# Connector_A.net
KiCad netlist of a schematic drawn in Altium Designer
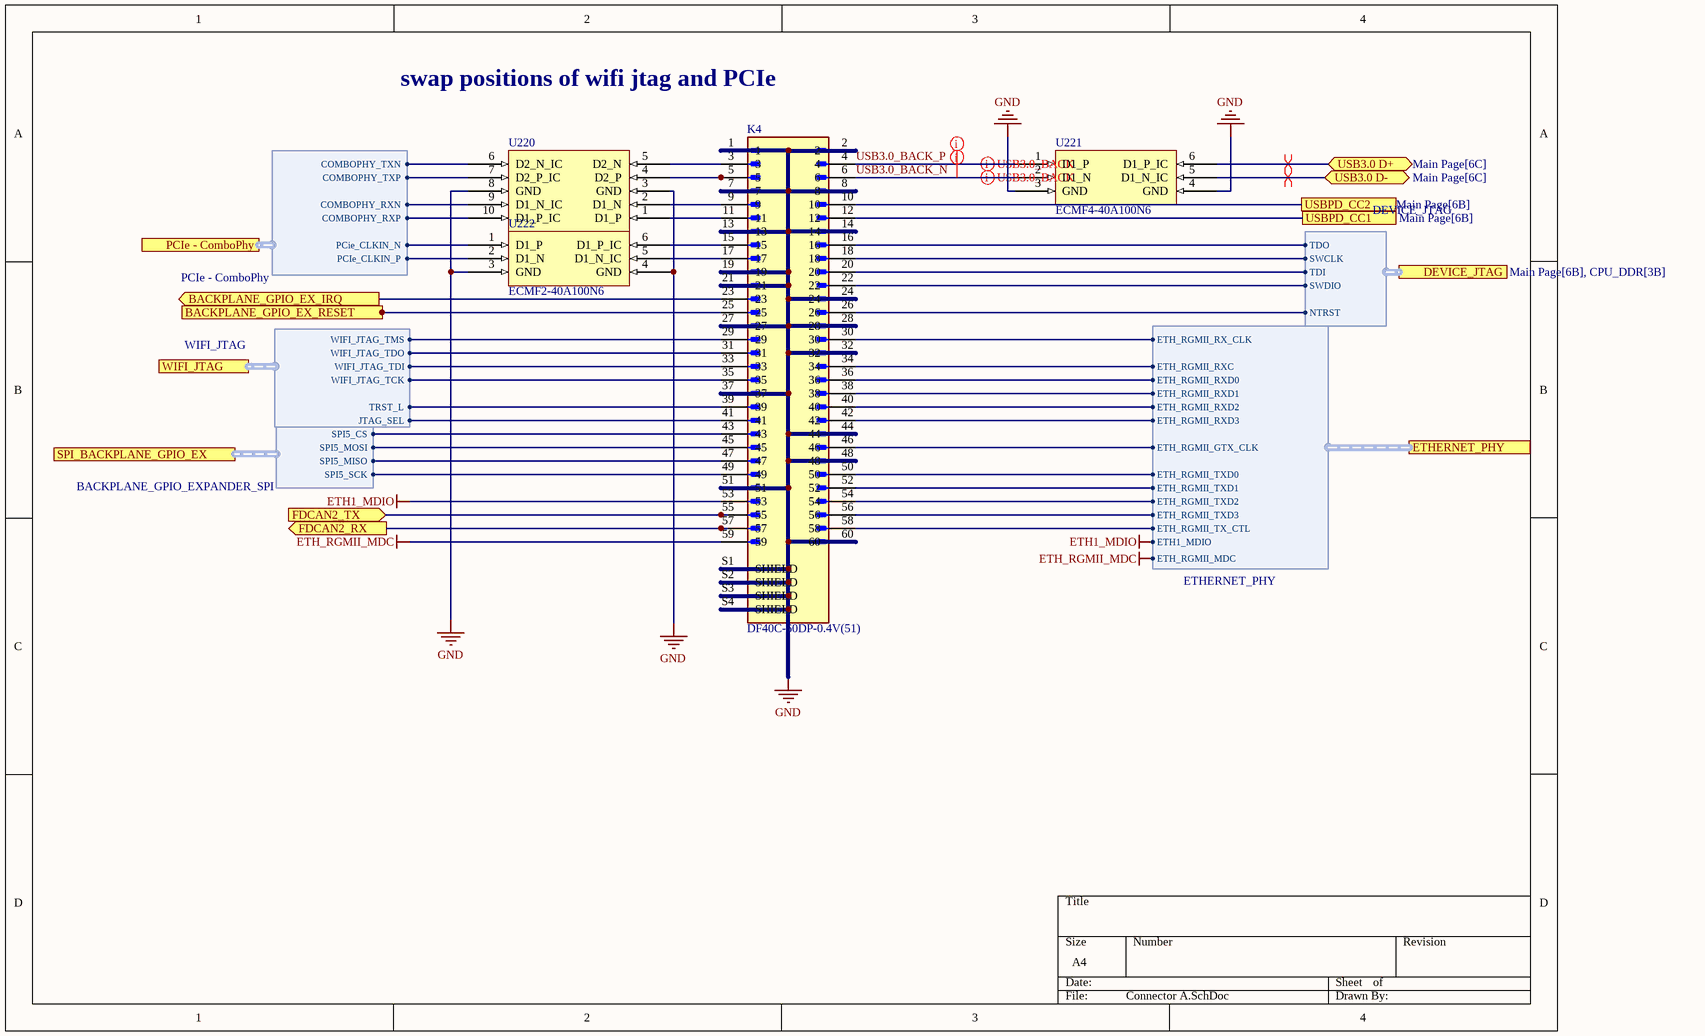
[diagram p0: Connector A.SchDoc]

(export (version "E")
  (design (tool "Eeschema 10.0.6"))
  (components
    (comp (ref "K4")
      (value "DF40C-60DP-0.4V(51)")
      (footprint "HIROSE_DF40C-60DP-0.4V(51)")
      (description "60 Position Connector Plug, Outer Shroud Contacts Surface Mount Gold")
      (fields (field (name "MF") "Hirose Electric"))
      (libsource (lib "Gesturelink Schematic Library") (part "DF40C-60DP-0.4V(51)"))
    )
    (comp (ref "U220")
      (value "ECMF4-40A100N10")
      (footprint "ECMF4-40A100N10")
      (description "4 Line Common Mode Choke Surface Mount 100mA DCR 3Ohm (Typ)")
      (libsource (lib "Gesturelink Schematic Library") (part "ECMF4-40A100N10"))
    )
    (comp (ref "U221")
      (value "ECMF4-40A100N6")
      (footprint "ECMF2-40A100N6")
      (description "2 Line Common Mode Choke Surface Mount 100mA DCR 3Ohm (Typ)")
      (libsource (lib "Gesturelink Schematic Library") (part "ECMF4-40A100N6"))
    )
    (comp (ref "U222")
      (value "ECMF2-40A100N6")
      (footprint "ECMF2-40A100N6")
      (description "2 Line Common Mode Choke Surface Mount 100mA DCR 3Ohm (Typ)")
      (libsource (lib "Gesturelink Schematic Library") (part "ECMF2-40A100N6"))
    )
  )
  (nets
    (net (code "8") (name "/BACKPLANE_GPIO_EX_IRQ") (class "Default")
      (node (ref "K4") (pin "23") (pinfunction "23_23") (pintype "passive"))
    )
    (net (code "9") (name "/BACKPLANE_GPIO_EX_RESET") (class "Default")
      (node (ref "K4") (pin "25") (pinfunction "25_25") (pintype "passive"))
    )
    (net (code "10") (name "/COMBOPHY_RXN") (class "Default")
      (node (ref "U220") (pin "9") (pinfunction "D1_N_IC_9") (pintype "input"))
    )
    (net (code "11") (name "/COMBOPHY_RXP") (class "Default")
      (node (ref "U220") (pin "10") (pinfunction "D1_P_IC_10") (pintype "input"))
    )
    (net (code "12") (name "/COMBOPHY_TXN") (class "Default")
      (node (ref "U220") (pin "6") (pinfunction "D2_N_IC_6") (pintype "input"))
    )
    (net (code "13") (name "/COMBOPHY_TXP") (class "Default")
      (node (ref "U220") (pin "7") (pinfunction "D2_P_IC_7") (pintype "input"))
    )
    (net (code "14") (name "/ETH_RGMII_GTX_CLK") (class "Default")
      (node (ref "K4") (pin "46") (pinfunction "46_46") (pintype "passive"))
    )
    (net (code "15") (name "/ETH_RGMII_RXC") (class "Default")
      (node (ref "K4") (pin "34") (pinfunction "34_34") (pintype "passive"))
    )
    (net (code "16") (name "/ETH_RGMII_RXD0") (class "Default")
      (node (ref "K4") (pin "36") (pinfunction "36_36") (pintype "passive"))
    )
    (net (code "17") (name "/ETH_RGMII_RXD1") (class "Default")
      (node (ref "K4") (pin "38") (pinfunction "38_38") (pintype "passive"))
    )
    (net (code "18") (name "/ETH_RGMII_RXD2") (class "Default")
      (node (ref "K4") (pin "40") (pinfunction "40_40") (pintype "passive"))
    )
    (net (code "19") (name "/ETH_RGMII_RXD3") (class "Default")
      (node (ref "K4") (pin "42") (pinfunction "42_42") (pintype "passive"))
    )
    (net (code "20") (name "/ETH_RGMII_RX_CLK") (class "Default")
      (node (ref "K4") (pin "30") (pinfunction "30_30") (pintype "passive"))
    )
    (net (code "21") (name "/ETH_RGMII_TXD0") (class "Default")
      (node (ref "K4") (pin "50") (pinfunction "50_50") (pintype "passive"))
    )
    (net (code "22") (name "/ETH_RGMII_TXD1") (class "Default")
      (node (ref "K4") (pin "52") (pinfunction "52_52") (pintype "passive"))
    )
    (net (code "23") (name "/ETH_RGMII_TXD2") (class "Default")
      (node (ref "K4") (pin "54") (pinfunction "54_54") (pintype "passive"))
    )
    (net (code "24") (name "/ETH_RGMII_TXD3") (class "Default")
      (node (ref "K4") (pin "56") (pinfunction "56_56") (pintype "passive"))
    )
    (net (code "25") (name "/ETH_RGMII_TX_CTL") (class "Default")
      (node (ref "K4") (pin "58") (pinfunction "58_58") (pintype "passive"))
    )
    (net (code "26") (name "/FDCAN2_RX") (class "Default")
      (node (ref "K4") (pin "57") (pinfunction "57_57") (pintype "passive"))
    )
    (net (code "27") (name "/FDCAN2_TX") (class "Default")
      (node (ref "K4") (pin "55") (pinfunction "55_55") (pintype "passive"))
    )
    (net (code "28") (name "/JTAG_SEL") (class "Default")
      (node (ref "K4") (pin "41") (pinfunction "41_41") (pintype "passive"))
    )
    (net (code "29") (name "/NTRST") (class "Default")
      (node (ref "K4") (pin "26") (pinfunction "26_26") (pintype "passive"))
    )
    (net (code "30") (name "/PCIe_CLKIN_P") (class "Default")
      (node (ref "U222") (pin "2") (pinfunction "D1_N_2") (pintype "input"))
    )
    (net (code "31") (name "/PCie_CLKIN_N") (class "Default")
      (node (ref "U222") (pin "1") (pinfunction "D1_P_1") (pintype "input"))
    )
    (net (code "32") (name "/SPI5_CS") (class "Default")
      (node (ref "K4") (pin "43") (pinfunction "43_43") (pintype "passive"))
    )
    (net (code "33") (name "/SPI5_MISO") (class "Default")
      (node (ref "K4") (pin "47") (pinfunction "47_47") (pintype "passive"))
    )
    (net (code "34") (name "/SPI5_MOSI") (class "Default")
      (node (ref "K4") (pin "45") (pinfunction "45_45") (pintype "passive"))
    )
    (net (code "35") (name "/SPI5_SCK") (class "Default")
      (node (ref "K4") (pin "49") (pinfunction "49_49") (pintype "passive"))
    )
    (net (code "36") (name "/SWCLK") (class "Default")
      (node (ref "K4") (pin "18") (pinfunction "18_18") (pintype "passive"))
    )
    (net (code "37") (name "/SWDIO") (class "Default")
      (node (ref "K4") (pin "22") (pinfunction "22_22") (pintype "passive"))
    )
    (net (code "38") (name "/TDI") (class "Default")
      (node (ref "K4") (pin "20") (pinfunction "20_20") (pintype "passive"))
    )
    (net (code "39") (name "/TDO") (class "Default")
      (node (ref "K4") (pin "16") (pinfunction "16_16") (pintype "passive"))
    )
    (net (code "40") (name "/TRST_L") (class "Default")
      (node (ref "K4") (pin "39") (pinfunction "39_39") (pintype "passive"))
    )
    (net (code "41") (name "/USB3.0 D+") (class "Default")
      (node (ref "U221") (pin "6") (pinfunction "D1_P_IC_6") (pintype "input"))
    )
    (net (code "42") (name "/USB3.0 D-") (class "Default")
      (node (ref "U221") (pin "5") (pinfunction "D1_N_IC_5") (pintype "input"))
    )
    (net (code "43") (name "/USB3.0_BACK_N") (class "Default")
      (node (ref "K4") (pin "6") (pinfunction "6_6") (pintype "passive"))
      (node (ref "U221") (pin "2") (pinfunction "D1_N_2") (pintype "input"))
    )
    (net (code "44") (name "/USB3.0_BACK_P") (class "Default")
      (node (ref "K4") (pin "4") (pinfunction "4_4") (pintype "passive"))
      (node (ref "U221") (pin "1") (pinfunction "D1_P_1") (pintype "input"))
    )
    (net (code "45") (name "/USBPD_CC1") (class "Default")
      (node (ref "K4") (pin "12") (pinfunction "12_12") (pintype "passive"))
    )
    (net (code "46") (name "/USBPD_CC2") (class "Default")
      (node (ref "K4") (pin "10") (pinfunction "10_10") (pintype "passive"))
    )
    (net (code "47") (name "/WIFI_JTAG_TCK") (class "Default")
      (node (ref "K4") (pin "35") (pinfunction "35_35") (pintype "passive"))
    )
    (net (code "48") (name "/WIFI_JTAG_TDI") (class "Default")
      (node (ref "K4") (pin "33") (pinfunction "33_33") (pintype "passive"))
    )
    (net (code "49") (name "/WIFI_JTAG_TDO") (class "Default")
      (node (ref "K4") (pin "31") (pinfunction "31_31") (pintype "passive"))
    )
    (net (code "50") (name "/WIFI_JTAG_TMS") (class "Default")
      (node (ref "K4") (pin "29") (pinfunction "29_29") (pintype "passive"))
    )
    (net (code "56") (name "ETH1_MDIO") (class "Default")
      (node (ref "K4") (pin "53") (pinfunction "53_53") (pintype "passive"))
    )
    (net (code "57") (name "ETH_RGMII_MDC") (class "Default")
      (node (ref "K4") (pin "59") (pinfunction "59_59") (pintype "passive"))
    )
    (net (code "58") (name "GND") (class "Default")
      (node (ref "K4") (pin "1") (pinfunction "1_1") (pintype "passive"))
      (node (ref "K4") (pin "13") (pinfunction "13_13") (pintype "passive"))
      (node (ref "K4") (pin "14") (pinfunction "14_14") (pintype "passive"))
      (node (ref "K4") (pin "19") (pinfunction "19_19") (pintype "passive"))
      (node (ref "K4") (pin "2") (pinfunction "2_2") (pintype "passive"))
      (node (ref "K4") (pin "21") (pinfunction "21_21") (pintype "passive"))
      (node (ref "K4") (pin "24") (pinfunction "24_24") (pintype "passive"))
      (node (ref "K4") (pin "27") (pinfunction "27_27") (pintype "passive"))
      (node (ref "K4") (pin "28") (pinfunction "28_28") (pintype "passive"))
      (node (ref "K4") (pin "32") (pinfunction "32_32") (pintype "passive"))
      (node (ref "K4") (pin "37") (pinfunction "37_37") (pintype "passive"))
      (node (ref "K4") (pin "44") (pinfunction "44_44") (pintype "passive"))
      (node (ref "K4") (pin "48") (pinfunction "48_48") (pintype "passive"))
      (node (ref "K4") (pin "51") (pinfunction "51_51") (pintype "passive"))
      (node (ref "K4") (pin "60") (pinfunction "60_60") (pintype "passive"))
      (node (ref "K4") (pin "7") (pinfunction "7_7") (pintype "passive"))
      (node (ref "K4") (pin "8") (pinfunction "8_8") (pintype "passive"))
      (node (ref "K4") (pin "S1") (pinfunction "SHIELD_S1") (pintype "passive"))
      (node (ref "K4") (pin "S2") (pinfunction "SHIELD_S2") (pintype "passive"))
      (node (ref "K4") (pin "S3") (pinfunction "SHIELD_S3") (pintype "passive"))
      (node (ref "K4") (pin "S4") (pinfunction "SHIELD_S4") (pintype "passive"))
      (node (ref "U220") (pin "3") (pinfunction "GND_3") (pintype "input"))
      (node (ref "U220") (pin "8") (pinfunction "GND_8") (pintype "input"))
      (node (ref "U221") (pin "3") (pinfunction "GND_3") (pintype "input"))
      (node (ref "U221") (pin "4") (pinfunction "GND_4") (pintype "input"))
      (node (ref "U222") (pin "3") (pinfunction "GND_3") (pintype "input"))
      (node (ref "U222") (pin "4") (pinfunction "GND_4") (pintype "input"))
    )
    (net (code "59") (name "Net-(U220-D1_N)") (class "Default")
      (node (ref "K4") (pin "9") (pinfunction "9_9") (pintype "passive"))
      (node (ref "U220") (pin "2") (pinfunction "D1_N_2") (pintype "input"))
    )
    (net (code "60") (name "Net-(U220-D1_P)") (class "Default")
      (node (ref "K4") (pin "11") (pinfunction "11_11") (pintype "passive"))
      (node (ref "U220") (pin "1") (pinfunction "D1_P_1") (pintype "input"))
    )
    (net (code "61") (name "Net-(U220-D2_N)") (class "Default")
      (node (ref "K4") (pin "3") (pinfunction "3_3") (pintype "passive"))
      (node (ref "U220") (pin "5") (pinfunction "D2_N_5") (pintype "input"))
    )
    (net (code "62") (name "Net-(U220-D2_P)") (class "Default")
      (node (ref "K4") (pin "5") (pinfunction "5_5") (pintype "passive"))
      (node (ref "U220") (pin "4") (pinfunction "D2_P_4") (pintype "input"))
    )
    (net (code "63") (name "Net-(U222-D1_N_IC)") (class "Default")
      (node (ref "K4") (pin "17") (pinfunction "17_17") (pintype "passive"))
      (node (ref "U222") (pin "5") (pinfunction "D1_N_IC_5") (pintype "input"))
    )
    (net (code "64") (name "Net-(U222-D1_P_IC)") (class "Default")
      (node (ref "K4") (pin "15") (pinfunction "15_15") (pintype "passive"))
      (node (ref "U222") (pin "6") (pinfunction "D1_P_IC_6") (pintype "input"))
    )
  )
)
